# BusinessCardPCB.net
KiCad netlist of a schematic drawn in Altium Designer
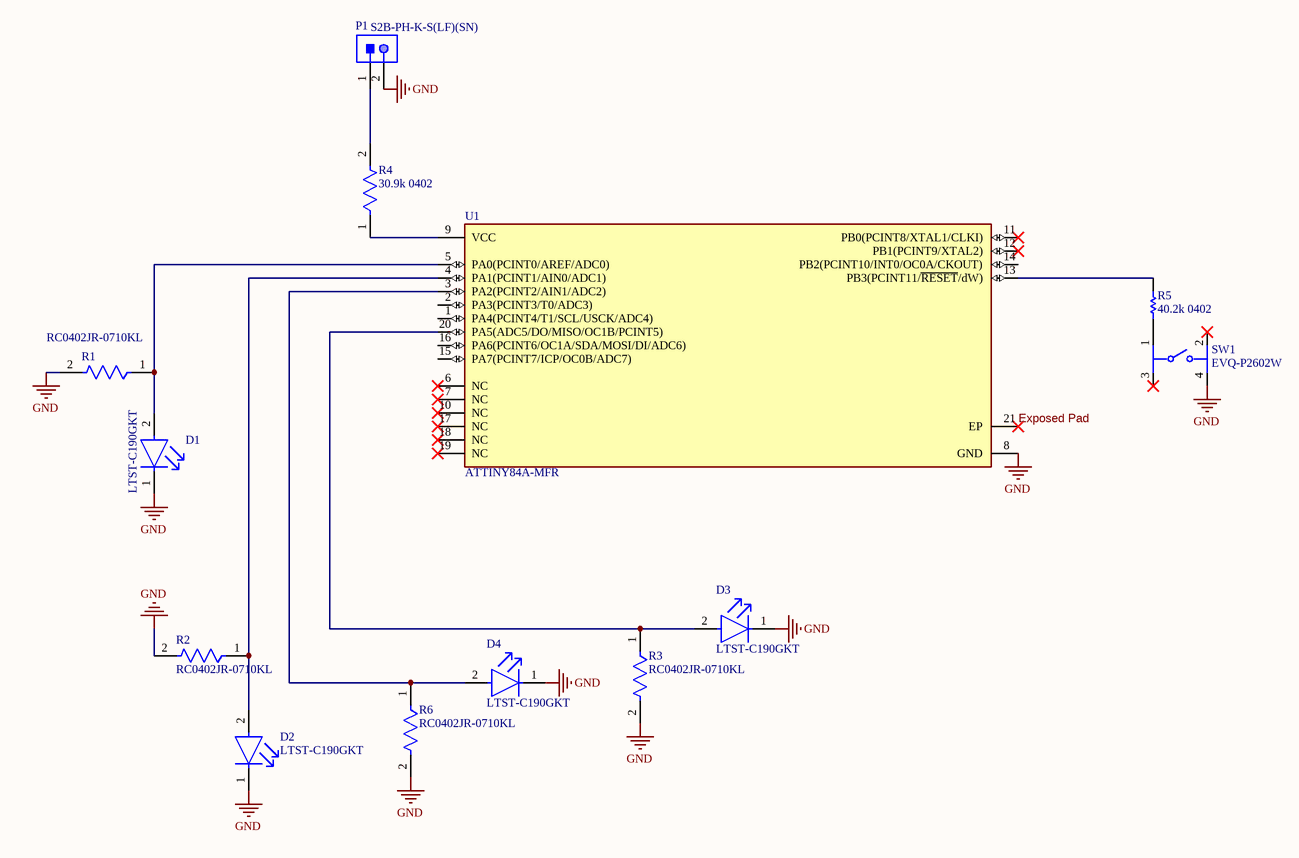
[diagram p0: BusinessCardPCB.SchDoc]

(export (version "E")
  (design (tool "Eeschema 10.0.6"))
  (components
    (comp (ref "D1")
      (value "LTST-C190GKT")
      (footprint "FP-LTST-C190GKT-MFG")
      (description "LED GREEN CLEAR CHIP SMD")
      (fields (field (name "VOLTAGE") "2V"))
      (libsource (lib "Altium Content Vault") (part "8706943c75ba83719d021d2fdc84c58"))
    )
    (comp (ref "D2")
      (value "LTST-C190GKT")
      (footprint "FP-LTST-C190GKT-MFG")
      (description "LED GREEN CLEAR CHIP SMD")
      (fields (field (name "VOLTAGE") "2V"))
      (libsource (lib "Altium Content Vault") (part "8706943c75ba83719d021d2fdc84c58"))
    )
    (comp (ref "D3")
      (value "LTST-C190GKT")
      (footprint "FP-LTST-C190GKT-MFG")
      (description "LED GREEN CLEAR CHIP SMD")
      (fields (field (name "VOLTAGE") "2V"))
      (libsource (lib "Altium Content Vault") (part "8706943c75ba83719d021d2fdc84c58"))
    )
    (comp (ref "D4")
      (value "LTST-C190GKT")
      (footprint "FP-LTST-C190GKT-MFG")
      (description "LED GREEN CLEAR CHIP SMD")
      (fields (field (name "VOLTAGE") "2V"))
      (libsource (lib "Altium Content Vault") (part "8706943c75ba83719d021d2fdc84c58"))
    )
    (comp (ref "P1")
      (value "S2B-PH-K-S(LF)(SN)")
      (footprint "JST-S2B-PH-K-S_V")
      (fields (field (name "TOLERANCE") "20%"))
      (libsource (lib "Altium Content Vault") (part "CN-1P-M-R2"))
    )
    (comp (ref "R1")
      (value "RC0402JR-0710KL")
      (footprint "FP-RC0402-0_4-IPC_C")
      (description "RES 10K OHM 5% 1/16W 0402")
      (fields (field (name "TOLERANCE") "5%"))
      (libsource (lib "Altium Content Vault") (part "1029c3af85768c4190bb7ad29bc67b5"))
    )
    (comp (ref "R2")
      (value "RC0402JR-0710KL")
      (footprint "FP-RC0402-0_4-IPC_C")
      (description "RES 10K OHM 5% 1/16W 0402")
      (fields (field (name "TOLERANCE") "5%"))
      (libsource (lib "Altium Content Vault") (part "1029c3af85768c4190bb7ad29bc67b5"))
    )
    (comp (ref "R3")
      (value "RC0402JR-0710KL")
      (footprint "FP-RC0402-0_4-IPC_C")
      (description "RES 10K OHM 5% 1/16W 0402")
      (fields (field (name "TOLERANCE") "5%"))
      (libsource (lib "Altium Content Vault") (part "1029c3af85768c4190bb7ad29bc67b5"))
    )
    (comp (ref "R4")
      (value "30.9k 0402")
      (footprint "FP-RT0402-MFG")
      (description "RES SMD 30.9KOHM 0.1% 1/16W 0402")
      (fields
        (field (name "MANUFACTURER PART NUMBER") "RT0402BRE0730K9L")
        (field (name "MANUFACTURER") "Yageo")
      )
      (libsource (lib "Altium Content Vault") (part "1029c3af85768c4190bb7ad29bc67b5"))
    )
    (comp (ref "R5")
      (value "40.2k 0402")
      (footprint "RESC1005X40X25ML05T10")
      (fields (field (name "PART NUMBER") "RC0402FR-0740K2L") (field (name "MANUFACTURER") "Yageo / Phycomp"))
      (libsource (lib "Altium Content Vault") (part "RES"))
    )
    (comp (ref "R6")
      (value "RC0402JR-0710KL")
      (footprint "FP-RC0402-0_4-IPC_C")
      (description "RES 10K OHM 5% 1/16W 0402")
      (fields (field (name "TOLERANCE") "5%"))
      (libsource (lib "Altium Content Vault") (part "1029c3af85768c4190bb7ad29bc67b5"))
    )
    (comp (ref "SW1")
      (value "EVQ-P2602W")
      (footprint "FP-EVQ-P2602W-MFG")
      (description "EVQ-P2602W Switch Tactile N.O. SPST Button J-Bend 0.02A 15VDC 3.5N SMD Automotive Embossed T/R")
      (libsource (lib "Altium Content Vault") (part "cb67941ecbda1860b707deecc235d4d"))
    )
    (comp (ref "U1")
      (value "ATTINY84A-MFR")
      (footprint "FP-C04-21443-MFG")
      (description "ATTINY84A-MFR AVR, 8K FLASH 2K SRAM, 1KB EEPROM - 16MHz, 4x4WQFN, High Grade +125C, Green, T&R")
      (libsource (lib "Altium Content Vault") (part "3cf7b43ae09d1a7a44b20cb57b0a53b"))
    )
  )
  (nets
    (net (code "1") (name "/Exposed Pad") (class "Default")
      (node (ref "U1") (pin "21") (pinfunction "EP_21") (pintype "passive+no_connect"))
    )
    (net (code "2") (name "GND") (class "Default")
      (node (ref "D1") (pin "1") (pinfunction "C_1") (pintype "passive"))
      (node (ref "D2") (pin "1") (pinfunction "C_1") (pintype "passive"))
      (node (ref "D3") (pin "1") (pinfunction "C_1") (pintype "passive"))
      (node (ref "D4") (pin "1") (pinfunction "C_1") (pintype "passive"))
      (node (ref "P1") (pin "2") (pinfunction "2_2") (pintype "passive"))
      (node (ref "R1") (pin "2") (pinfunction "2_2") (pintype "passive"))
      (node (ref "R2") (pin "2") (pinfunction "2_2") (pintype "passive"))
      (node (ref "R3") (pin "2") (pinfunction "2_2") (pintype "passive"))
      (node (ref "R6") (pin "2") (pinfunction "2_2") (pintype "passive"))
      (node (ref "SW1") (pin "4") (pinfunction "4_4") (pintype "passive"))
      (node (ref "U1") (pin "8") (pinfunction "GND_8") (pintype "power_in"))
    )
    (net (code "3") (name "Net-(D1-A)") (class "Default")
      (node (ref "D1") (pin "2") (pinfunction "A_2") (pintype "passive"))
      (node (ref "R1") (pin "1") (pinfunction "1_1") (pintype "passive"))
      (node (ref "U1") (pin "5") (pinfunction "PA0(PCINT0/AREF/ADC0)_5") (pintype "bidirectional"))
    )
    (net (code "4") (name "Net-(D2-A)") (class "Default")
      (node (ref "D2") (pin "2") (pinfunction "A_2") (pintype "passive"))
      (node (ref "R2") (pin "1") (pinfunction "1_1") (pintype "passive"))
      (node (ref "U1") (pin "4") (pinfunction "PA1(PCINT1/AIN0/ADC1)_4") (pintype "bidirectional"))
    )
    (net (code "5") (name "Net-(D3-A)") (class "Default")
      (node (ref "D3") (pin "2") (pinfunction "A_2") (pintype "passive"))
      (node (ref "R3") (pin "1") (pinfunction "1_1") (pintype "passive"))
      (node (ref "U1") (pin "20") (pinfunction "PA5(ADC5/DO/MISO/OC1B/PCINT5)_20") (pintype "bidirectional"))
    )
    (net (code "6") (name "Net-(D4-A)") (class "Default")
      (node (ref "D4") (pin "2") (pinfunction "A_2") (pintype "passive"))
      (node (ref "R6") (pin "1") (pinfunction "1_1") (pintype "passive"))
      (node (ref "U1") (pin "3") (pinfunction "PA2(PCINT2/AIN1/ADC2)_3") (pintype "bidirectional"))
    )
    (net (code "7") (name "Net-(P1-Pad1)") (class "Default")
      (node (ref "P1") (pin "1") (pinfunction "1_1") (pintype "passive"))
      (node (ref "R4") (pin "2") (pinfunction "2_2") (pintype "passive"))
    )
    (net (code "8") (name "Net-(R5-Pad1)") (class "Default")
      (node (ref "R5") (pin "1") (pinfunction "1_1") (pintype "passive"))
      (node (ref "SW1") (pin "1") (pinfunction "1_1") (pintype "passive"))
    )
    (net (code "9") (name "Net-(U1-PB3(PCINT11{slash}~{RESET}{slash}dW))") (class "Default")
      (node (ref "R5") (pin "2") (pinfunction "2_2") (pintype "passive"))
      (node (ref "U1") (pin "13") (pinfunction "PB3(PCINT11/~{RESET}/dW)_13") (pintype "bidirectional"))
    )
    (net (code "10") (name "Net-(U1-VCC)") (class "Default")
      (node (ref "R4") (pin "1") (pinfunction "1_1") (pintype "passive"))
      (node (ref "U1") (pin "9") (pinfunction "VCC_9") (pintype "power_in"))
    )
    (net (code "11") (name "unconnected-(SW1-Pad2)") (class "Default")
      (node (ref "SW1") (pin "2") (pinfunction "2_2") (pintype "passive+no_connect"))
    )
    (net (code "12") (name "unconnected-(SW1-Pad3)") (class "Default")
      (node (ref "SW1") (pin "3") (pinfunction "3_3") (pintype "passive+no_connect"))
    )
    (net (code "13") (name "unconnected-(U1-NC-Pad6)") (class "Default")
      (node (ref "U1") (pin "6") (pinfunction "NC_6") (pintype "passive+no_connect"))
    )
    (net (code "14") (name "unconnected-(U1-NC-Pad7)") (class "Default")
      (node (ref "U1") (pin "7") (pinfunction "NC_7") (pintype "passive+no_connect"))
    )
    (net (code "15") (name "unconnected-(U1-NC-Pad10)") (class "Default")
      (node (ref "U1") (pin "10") (pinfunction "NC_10") (pintype "passive+no_connect"))
    )
    (net (code "16") (name "unconnected-(U1-NC-Pad17)") (class "Default")
      (node (ref "U1") (pin "17") (pinfunction "NC_17") (pintype "passive+no_connect"))
    )
    (net (code "17") (name "unconnected-(U1-NC-Pad18)") (class "Default")
      (node (ref "U1") (pin "18") (pinfunction "NC_18") (pintype "passive+no_connect"))
    )
    (net (code "18") (name "unconnected-(U1-NC-Pad19)") (class "Default")
      (node (ref "U1") (pin "19") (pinfunction "NC_19") (pintype "passive+no_connect"))
    )
    (net (code "19") (name "unconnected-(U1-PA3(PCINT3{slash}T0{slash}ADC3)-Pad2)") (class "Default")
      (node (ref "U1") (pin "2") (pinfunction "PA3(PCINT3/T0/ADC3)_2") (pintype "bidirectional"))
    )
    (net (code "20") (name "unconnected-(U1-PA4(PCINT4{slash}T1{slash}SCL{slash}USCK{slash}ADC4)-Pad1)") (class "Default")
      (node (ref "U1") (pin "1") (pinfunction "PA4(PCINT4/T1/SCL/USCK/ADC4)_1") (pintype "bidirectional"))
    )
    (net (code "21") (name "unconnected-(U1-PA6(PCINT6{slash}OC1A{slash}SDA{slash}MOSI{slash}DI{slash}ADC6)-Pad16)") (class "Default")
      (node (ref "U1") (pin "16") (pinfunction "PA6(PCINT6/OC1A/SDA/MOSI/DI/ADC6)_16") (pintype "bidirectional"))
    )
    (net (code "22") (name "unconnected-(U1-PA7(PCINT7{slash}ICP{slash}OC0B{slash}ADC7)-Pad15)") (class "Default")
      (node (ref "U1") (pin "15") (pinfunction "PA7(PCINT7/ICP/OC0B/ADC7)_15") (pintype "bidirectional"))
    )
    (net (code "23") (name "unconnected-(U1-PB0(PCINT8{slash}XTAL1{slash}CLKI)-Pad11)") (class "Default")
      (node (ref "U1") (pin "11") (pinfunction "PB0(PCINT8/XTAL1/CLKI)_11") (pintype "bidirectional+no_connect"))
    )
    (net (code "24") (name "unconnected-(U1-PB1(PCINT9{slash}XTAL2)-Pad12)") (class "Default")
      (node (ref "U1") (pin "12") (pinfunction "PB1(PCINT9/XTAL2)_12") (pintype "bidirectional+no_connect"))
    )
    (net (code "25") (name "unconnected-(U1-PB2(PCINT10{slash}INT0{slash}OC0A{slash}CKOUT)-Pad14)") (class "Default")
      (node (ref "U1") (pin "14") (pinfunction "PB2(PCINT10/INT0/OC0A/CKOUT)_14") (pintype "bidirectional"))
    )
  )
)
